# IF_amp.net
KiCad netlist of a schematic drawn in Altium Designer
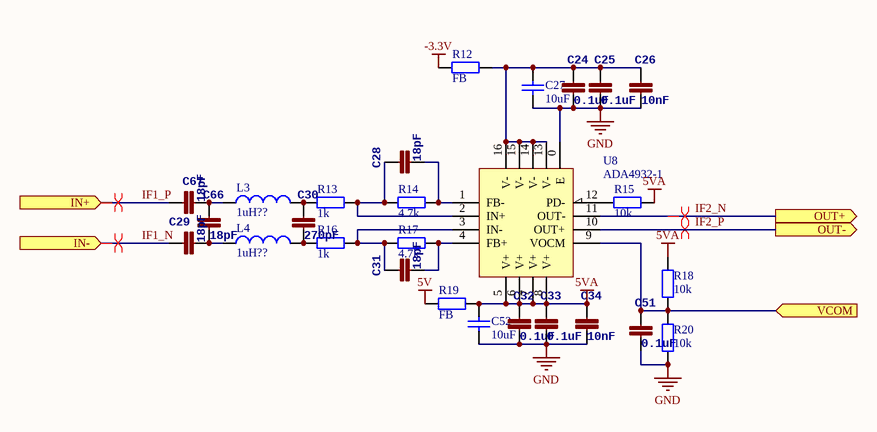
[diagram p0: IF_amp.SchDoc]

(export (version "E")
  (design (tool "Eeschema 10.0.6"))
  (components
    (comp (ref "C24")
      (value "0.1uF")
      (footprint "0402")
      (description "<b>Capacitor</b>\nStandard 0603 ceramic capacitor, and 0.1\" leaded capacitor.")
      (fields (field (name "PARTNO") "CC0402ZRY5V7BB104"))
      (libsource (lib "*") (part "CAP0402-CAP"))
    )
    (comp (ref "C25")
      (value "0.1uF")
      (footprint "0402")
      (description "<b>Capacitor</b>\nStandard 0603 ceramic capacitor, and 0.1\" leaded capacitor.")
      (fields (field (name "PARTNO") "CC0402ZRY5V7BB104"))
      (libsource (lib "*") (part "CAP0402-CAP"))
    )
    (comp (ref "C26")
      (value "10nF")
      (footprint "0402")
      (description "<b>Capacitor</b>\nStandard 0603 ceramic capacitor, and 0.1\" leaded capacitor.")
      (fields (field (name "PARTNO") "CC0402ZRY5V7BB104"))
      (libsource (lib "*") (part "CAP0402-CAP"))
    )
    (comp (ref "C27")
      (value "10uF")
      (footprint "0805")
      (description "Capacitor")
      (fields (field (name "PUBLISHER") "Altium Limited"))
      (libsource (lib "RTC6705") (part "Cap"))
    )
    (comp (ref "C28")
      (value "18pF")
      (footprint "0402")
      (description "<b>Capacitor</b>\nStandard 0603 ceramic capacitor, and 0.1\" leaded capacitor.")
      (fields (field (name "PARTNO") "CC0402ZRY5V7BB104"))
      (libsource (lib "") (part "CAP0402-CAP_1"))
    )
    (comp (ref "C29")
      (value "18pF")
      (footprint "0402")
      (description "<b>Capacitor</b>\nStandard 0603 ceramic capacitor, and 0.1\" leaded capacitor.")
      (fields (field (name "PARTNO") "CC0402ZRY5V7BB104"))
      (libsource (lib "") (part "CAP0402-CAP_1"))
    )
    (comp (ref "C30")
      (value "270pF")
      (footprint "0402")
      (description "<b>Capacitor</b>\nStandard 0603 ceramic capacitor, and 0.1\" leaded capacitor.")
      (fields (field (name "PARTNO") "CC0402ZRY5V7BB104"))
      (libsource (lib "*") (part "CAP0402-CAP"))
    )
    (comp (ref "C31")
      (value "18pF")
      (footprint "0402")
      (description "<b>Capacitor</b>\nStandard 0603 ceramic capacitor, and 0.1\" leaded capacitor.")
      (fields (field (name "PARTNO") "CC0402ZRY5V7BB104"))
      (libsource (lib "") (part "CAP0402-CAP_1"))
    )
    (comp (ref "C32")
      (value "0.1uF")
      (footprint "0402")
      (description "<b>Capacitor</b>\nStandard 0603 ceramic capacitor, and 0.1\" leaded capacitor.")
      (fields (field (name "PARTNO") "CC0402ZRY5V7BB104"))
      (libsource (lib "*") (part "CAP0402-CAP"))
    )
    (comp (ref "C33")
      (value "0.1uF")
      (footprint "0402")
      (description "<b>Capacitor</b>\nStandard 0603 ceramic capacitor, and 0.1\" leaded capacitor.")
      (fields (field (name "PARTNO") "CC0402ZRY5V7BB104"))
      (libsource (lib "*") (part "CAP0402-CAP"))
    )
    (comp (ref "C34")
      (value "10nF")
      (footprint "0402")
      (description "<b>Capacitor</b>\nStandard 0603 ceramic capacitor, and 0.1\" leaded capacitor.")
      (fields (field (name "PARTNO") "CC0402ZRY5V7BB104"))
      (libsource (lib "*") (part "CAP0402-CAP"))
    )
    (comp (ref "C51")
      (value "0.1uF")
      (footprint "0402")
      (description "<b>Capacitor</b>\nStandard 0603 ceramic capacitor, and 0.1\" leaded capacitor.")
      (fields (field (name "PARTNO") "CC0402ZRY5V7BB104"))
      (libsource (lib "*") (part "CAP0402-CAP"))
    )
    (comp (ref "C52")
      (value "10uF")
      (footprint "0805")
      (description "Capacitor")
      (fields (field (name "PUBLISHER") "Altium Limited"))
      (libsource (lib "RTC6705") (part "Cap"))
    )
    (comp (ref "C66")
      (value "18pF")
      (footprint "0402")
      (description "<b>Capacitor</b>\nStandard 0603 ceramic capacitor, and 0.1\" leaded capacitor.")
      (fields (field (name "PARTNO") "CC0402ZRY5V7BB104"))
      (libsource (lib "*") (part "CAP0402-CAP"))
    )
    (comp (ref "C67")
      (value "18pF")
      (footprint "0402")
      (description "<b>Capacitor</b>\nStandard 0603 ceramic capacitor, and 0.1\" leaded capacitor.")
      (fields (field (name "PARTNO") "CC0402ZRY5V7BB104"))
      (libsource (lib "") (part "CAP0402-CAP_1"))
    )
    (comp (ref "L3")
      (value "1uH??")
      (footprint "0805")
      (description "Inductor")
      (fields (field (name "PUBLISHER") "Altium Limited"))
      (libsource (lib "Miscellaneous Devices") (part "Inductor"))
    )
    (comp (ref "L4")
      (value "1uH??")
      (footprint "0805")
      (description "Inductor")
      (fields (field (name "PUBLISHER") "Altium Limited"))
      (libsource (lib "Miscellaneous Devices") (part "Inductor"))
    )
    (comp (ref "R12")
      (value "FB")
      (footprint "0603")
      (description "Resistor")
      (fields (field (name "PUBLISHER") "Altium Limited"))
      (libsource (lib "Miscellaneous Devices") (part "Res2"))
    )
    (comp (ref "R13")
      (value "1k")
      (footprint "0402")
      (description "Resistor")
      (fields (field (name "Comment") "Res2") (field (name "PUBLISHER") "Altium Limited"))
      (libsource (lib "RTC6705") (part "Res2"))
    )
    (comp (ref "R14")
      (value "4.7k")
      (footprint "0402")
      (description "Resistor")
      (fields (field (name "Comment") "Res2") (field (name "PUBLISHER") "Altium Limited"))
      (libsource (lib "RTC6705") (part "Res2"))
    )
    (comp (ref "R15")
      (value "10k")
      (footprint "0402")
      (description "Resistor")
      (fields (field (name "Comment") "Res2") (field (name "PUBLISHER") "Altium Limited"))
      (libsource (lib "RTC6705") (part "Res2"))
    )
    (comp (ref "R16")
      (value "1k")
      (footprint "0402")
      (description "Resistor")
      (fields (field (name "Comment") "Res2") (field (name "PUBLISHER") "Altium Limited"))
      (libsource (lib "RTC6705") (part "Res2"))
    )
    (comp (ref "R17")
      (value "4.7k")
      (footprint "0402")
      (description "Resistor")
      (fields (field (name "Comment") "Res2") (field (name "PUBLISHER") "Altium Limited"))
      (libsource (lib "RTC6705") (part "Res2"))
    )
    (comp (ref "R18")
      (value "10k")
      (footprint "0402")
      (description "Resistor")
      (fields (field (name "Comment") "Res2") (field (name "PUBLISHER") "Altium Limited"))
      (libsource (lib "") (part "Res2_1"))
    )
    (comp (ref "R19")
      (value "FB")
      (footprint "0603")
      (description "Resistor")
      (fields (field (name "PUBLISHER") "Altium Limited"))
      (libsource (lib "Miscellaneous Devices") (part "Res2"))
    )
    (comp (ref "R20")
      (value "10k")
      (footprint "0402")
      (description "Resistor")
      (fields (field (name "Comment") "Res2") (field (name "PUBLISHER") "Altium Limited"))
      (libsource (lib "") (part "Res2_1"))
    )
    (comp (ref "U8") (value "ADA4932-1") (footprint "ADA4932-1") (libsource (lib "F4SDR") (part "ADA4932-1")))
  )
  (nets
    (net (code "1") (name "-3.3V") (class "Default")
      (node (ref "R12") (pin "1") (pinfunction "1_1") (pintype "passive"))
    )
    (net (code "2") (name "/IF1_N") (class "Default")
      (node (ref "C29") (pin "2") (pinfunction "2_2") (pintype "passive"))
    )
    (net (code "3") (name "/IF1_P") (class "Default")
      (node (ref "C67") (pin "2") (pinfunction "2_2") (pintype "passive"))
    )
    (net (code "4") (name "/IF2_N") (class "Default")
      (node (ref "U8") (pin "11") (pinfunction "OUT-_11") (pintype "passive"))
    )
    (net (code "5") (name "/IF2_P") (class "Default")
      (node (ref "U8") (pin "10") (pinfunction "OUT+_10") (pintype "passive"))
    )
    (net (code "6") (name "/VCOM") (class "Default")
      (node (ref "C51") (pin "2") (pinfunction "2_2") (pintype "passive"))
      (node (ref "R18") (pin "1") (pinfunction "1_1") (pintype "passive"))
      (node (ref "R20") (pin "2") (pinfunction "2_2") (pintype "passive"))
      (node (ref "U8") (pin "9") (pinfunction "VOCM_9") (pintype "passive"))
    )
    (net (code "7") (name "5V") (class "Default")
      (node (ref "R19") (pin "1") (pinfunction "1_1") (pintype "passive"))
    )
    (net (code "8") (name "5VA") (class "Default")
      (node (ref "C32") (pin "2") (pinfunction "2_2") (pintype "passive"))
      (node (ref "C33") (pin "2") (pinfunction "2_2") (pintype "passive"))
      (node (ref "C34") (pin "2") (pinfunction "2_2") (pintype "passive"))
      (node (ref "C52") (pin "1") (pinfunction "1_1") (pintype "passive"))
      (node (ref "R15") (pin "2") (pinfunction "2_2") (pintype "passive"))
      (node (ref "R18") (pin "2") (pinfunction "2_2") (pintype "passive"))
      (node (ref "R19") (pin "2") (pinfunction "2_2") (pintype "passive"))
      (node (ref "U8") (pin "5") (pinfunction "V+_5") (pintype "passive"))
      (node (ref "U8") (pin "6") (pinfunction "V+_6") (pintype "passive"))
      (node (ref "U8") (pin "7") (pinfunction "V+_7") (pintype "passive"))
      (node (ref "U8") (pin "8") (pinfunction "V+_8") (pintype "passive"))
    )
    (net (code "9") (name "GND") (class "Default")
      (node (ref "C24") (pin "1") (pinfunction "1_1") (pintype "passive"))
      (node (ref "C25") (pin "1") (pinfunction "1_1") (pintype "passive"))
      (node (ref "C26") (pin "1") (pinfunction "1_1") (pintype "passive"))
      (node (ref "C27") (pin "2") (pinfunction "2_2") (pintype "passive"))
      (node (ref "C32") (pin "1") (pinfunction "1_1") (pintype "passive"))
      (node (ref "C33") (pin "1") (pinfunction "1_1") (pintype "passive"))
      (node (ref "C34") (pin "1") (pinfunction "1_1") (pintype "passive"))
      (node (ref "C51") (pin "1") (pinfunction "1_1") (pintype "passive"))
      (node (ref "C52") (pin "2") (pinfunction "2_2") (pintype "passive"))
      (node (ref "R20") (pin "1") (pinfunction "1_1") (pintype "passive"))
      (node (ref "U8") (pin "0") (pinfunction "E_0") (pintype "passive"))
    )
    (net (code "10") (name "Net-(C24-Pad2)") (class "Default")
      (node (ref "C24") (pin "2") (pinfunction "2_2") (pintype "passive"))
      (node (ref "C25") (pin "2") (pinfunction "2_2") (pintype "passive"))
      (node (ref "C26") (pin "2") (pinfunction "2_2") (pintype "passive"))
      (node (ref "C27") (pin "1") (pinfunction "1_1") (pintype "passive"))
      (node (ref "R12") (pin "2") (pinfunction "2_2") (pintype "passive"))
      (node (ref "U8") (pin "13") (pinfunction "V-_13") (pintype "passive"))
      (node (ref "U8") (pin "14") (pinfunction "V-_14") (pintype "passive"))
      (node (ref "U8") (pin "15") (pinfunction "V-_15") (pintype "passive"))
      (node (ref "U8") (pin "16") (pinfunction "V-_16") (pintype "passive"))
    )
    (net (code "11") (name "Net-(C29-Pad1)") (class "Default")
      (node (ref "C29") (pin "1") (pinfunction "1_1") (pintype "passive"))
      (node (ref "C66") (pin "1") (pinfunction "1_1") (pintype "passive"))
      (node (ref "L4") (pin "1") (pinfunction "1_1") (pintype "passive"))
    )
    (net (code "12") (name "Net-(C30-Pad1)") (class "Default")
      (node (ref "C30") (pin "1") (pinfunction "1_1") (pintype "passive"))
      (node (ref "L4") (pin "2") (pinfunction "2_2") (pintype "passive"))
      (node (ref "R16") (pin "1") (pinfunction "1_1") (pintype "passive"))
    )
    (net (code "13") (name "Net-(C30-Pad2)") (class "Default")
      (node (ref "C30") (pin "2") (pinfunction "2_2") (pintype "passive"))
      (node (ref "L3") (pin "2") (pinfunction "2_2") (pintype "passive"))
      (node (ref "R13") (pin "1") (pinfunction "1_1") (pintype "passive"))
    )
    (net (code "14") (name "Net-(C66-Pad2)") (class "Default")
      (node (ref "C66") (pin "2") (pinfunction "2_2") (pintype "passive"))
      (node (ref "C67") (pin "1") (pinfunction "1_1") (pintype "passive"))
      (node (ref "L3") (pin "1") (pinfunction "1_1") (pintype "passive"))
    )
    (net (code "15") (name "Net-(U8-FB+)") (class "Default")
      (node (ref "C31") (pin "1") (pinfunction "1_1") (pintype "passive"))
      (node (ref "R17") (pin "2") (pinfunction "2_2") (pintype "passive"))
      (node (ref "U8") (pin "4") (pinfunction "FB+_4") (pintype "passive"))
    )
    (net (code "16") (name "Net-(U8-FB-)") (class "Default")
      (node (ref "C28") (pin "1") (pinfunction "1_1") (pintype "passive"))
      (node (ref "R14") (pin "2") (pinfunction "2_2") (pintype "passive"))
      (node (ref "U8") (pin "1") (pinfunction "FB-_1") (pintype "passive"))
    )
    (net (code "17") (name "Net-(U8-IN+)") (class "Default")
      (node (ref "C28") (pin "2") (pinfunction "2_2") (pintype "passive"))
      (node (ref "R13") (pin "2") (pinfunction "2_2") (pintype "passive"))
      (node (ref "R14") (pin "1") (pinfunction "1_1") (pintype "passive"))
      (node (ref "U8") (pin "2") (pinfunction "IN+_2") (pintype "passive"))
    )
    (net (code "18") (name "Net-(U8-IN-)") (class "Default")
      (node (ref "C31") (pin "2") (pinfunction "2_2") (pintype "passive"))
      (node (ref "R16") (pin "2") (pinfunction "2_2") (pintype "passive"))
      (node (ref "R17") (pin "1") (pinfunction "1_1") (pintype "passive"))
      (node (ref "U8") (pin "3") (pinfunction "IN-_3") (pintype "passive"))
    )
    (net (code "19") (name "Net-(U8-PD-)") (class "Default")
      (node (ref "R15") (pin "1") (pinfunction "1_1") (pintype "passive"))
      (node (ref "U8") (pin "12") (pinfunction "PD-_12") (pintype "passive"))
    )
  )
)
